# schEncoders.net
KiCad netlist of a schematic drawn in Altium Designer
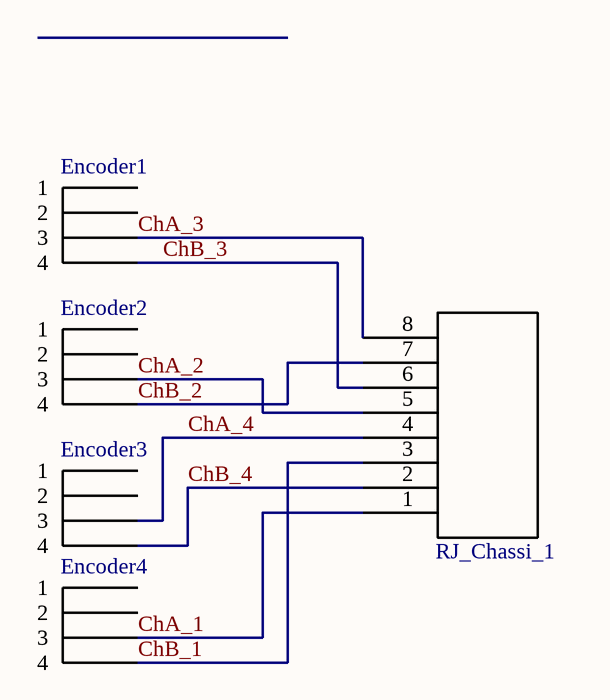
[diagram p0: schEncoders.SchDoc]

(export (version "E")
  (design (tool "Eeschema 10.0.6"))
  (components
    (comp (ref "Encoder1")
      (value "KK4")
      (footprint "4-vias")
      (libsource (lib "Componentes_Open") (part "KK4Vias"))
    )
    (comp (ref "Encoder2")
      (value "KK4")
      (footprint "4-vias")
      (libsource (lib "Componentes_Open") (part "KK4Vias"))
    )
    (comp (ref "Encoder3")
      (value "KK4")
      (footprint "4-vias")
      (libsource (lib "Componentes_Open") (part "KK4Vias"))
    )
    (comp (ref "Encoder4")
      (value "KK4")
      (footprint "4-vias")
      (libsource (lib "Componentes_Open") (part "KK4Vias"))
    )
    (comp (ref "RJ_Chassi_1")
      (value "RJ45")
      (footprint "RJ45_90")
      (libsource (lib "Componentes_Open") (part "RJ45_90"))
    )
  )
  (nets
    (net (code "1") (name "/ChA_1") (class "Default")
      (node (ref "Encoder4") (pin "3") (pinfunction "3_3") (pintype "passive"))
      (node (ref "RJ_Chassi_1") (pin "1") (pinfunction "9_1") (pintype "passive"))
    )
    (net (code "2") (name "/ChA_2") (class "Default")
      (node (ref "Encoder2") (pin "3") (pinfunction "3_3") (pintype "passive"))
      (node (ref "RJ_Chassi_1") (pin "5") (pinfunction "5_5") (pintype "passive"))
    )
    (net (code "3") (name "/ChA_3") (class "Default")
      (node (ref "Encoder1") (pin "3") (pinfunction "3_3") (pintype "passive"))
      (node (ref "RJ_Chassi_1") (pin "8") (pinfunction "8_8") (pintype "passive"))
    )
    (net (code "4") (name "/ChA_4") (class "Default")
      (node (ref "Encoder3") (pin "3") (pinfunction "3_3") (pintype "passive"))
      (node (ref "RJ_Chassi_1") (pin "4") (pinfunction "4_4") (pintype "passive"))
    )
    (net (code "5") (name "/ChB_1") (class "Default")
      (node (ref "Encoder4") (pin "4") (pinfunction "4_4") (pintype "passive"))
      (node (ref "RJ_Chassi_1") (pin "3") (pinfunction "3_3") (pintype "passive"))
    )
    (net (code "6") (name "/ChB_2") (class "Default")
      (node (ref "Encoder2") (pin "4") (pinfunction "4_4") (pintype "passive"))
      (node (ref "RJ_Chassi_1") (pin "7") (pinfunction "7_7") (pintype "passive"))
    )
    (net (code "7") (name "/ChB_3") (class "Default")
      (node (ref "Encoder1") (pin "4") (pinfunction "4_4") (pintype "passive"))
      (node (ref "RJ_Chassi_1") (pin "6") (pinfunction "6_6") (pintype "passive"))
    )
    (net (code "8") (name "/ChB_4") (class "Default")
      (node (ref "Encoder3") (pin "4") (pinfunction "4_4") (pintype "passive"))
      (node (ref "RJ_Chassi_1") (pin "2") (pinfunction "2_2") (pintype "passive"))
    )
    (net (code "9") (name "unconnected-(Encoder1-Pad1)") (class "Default")
      (node (ref "Encoder1") (pin "1") (pinfunction "1_1") (pintype "passive"))
    )
    (net (code "10") (name "unconnected-(Encoder1-Pad2)") (class "Default")
      (node (ref "Encoder1") (pin "2") (pinfunction "2_2") (pintype "passive"))
    )
    (net (code "11") (name "unconnected-(Encoder2-Pad1)") (class "Default")
      (node (ref "Encoder2") (pin "1") (pinfunction "1_1") (pintype "passive"))
    )
    (net (code "12") (name "unconnected-(Encoder2-Pad2)") (class "Default")
      (node (ref "Encoder2") (pin "2") (pinfunction "2_2") (pintype "passive"))
    )
    (net (code "13") (name "unconnected-(Encoder3-Pad1)") (class "Default")
      (node (ref "Encoder3") (pin "1") (pinfunction "1_1") (pintype "passive"))
    )
    (net (code "14") (name "unconnected-(Encoder3-Pad2)") (class "Default")
      (node (ref "Encoder3") (pin "2") (pinfunction "2_2") (pintype "passive"))
    )
    (net (code "15") (name "unconnected-(Encoder4-Pad1)") (class "Default")
      (node (ref "Encoder4") (pin "1") (pinfunction "1_1") (pintype "passive"))
    )
    (net (code "16") (name "unconnected-(Encoder4-Pad2)") (class "Default")
      (node (ref "Encoder4") (pin "2") (pinfunction "2_2") (pintype "passive"))
    )
  )
)
